# LM2576_BuckConverter.net
KiCad netlist of a schematic drawn in Altium Designer
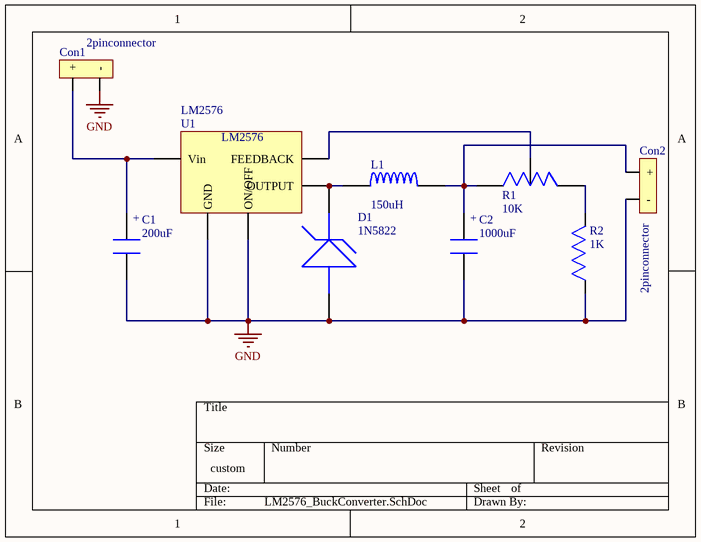
[diagram p0: LM2576_BuckConverter.SchDoc]

(export (version "E")
  (design (tool "Eeschema 10.0.6"))
  (components
    (comp (ref "C1")
      (value "200uF")
      (footprint "220uF Capacitor")
      (libsource (lib "LM2576_BuckConverter") (part "Electrolytic Cap 220uF"))
    )
    (comp (ref "C2")
      (value "1000uF")
      (footprint "1000Uf Cap")
      (libsource (lib "LM2576_BuckConverter") (part "Electrolytic Cap"))
    )
    (comp (ref "Con1")
      (value "2pinconnector")
      (footprint "2pin")
      (libsource (lib "LM2576_BuckConverter") (part "2pinconnector"))
    )
    (comp (ref "Con2")
      (value "2pinconnector")
      (footprint "2pin")
      (libsource (lib "") (part "2pinconnector_1"))
    )
    (comp (ref "D1")
      (value "1N5822")
      (footprint "1n5822")
      (libsource (lib "LM2576_BuckConverter") (part "1N5822"))
    )
    (comp (ref "L1")
      (value "150uH")
      (footprint "150uH Inductor")
      (libsource (lib "LM2576_BuckConverter") (part "150uH L"))
    )
    (comp (ref "R1")
      (value "10K")
      (footprint "10K Pot")
      (libsource (lib "LM2576_BuckConverter") (part "Variable Resistor"))
    )
    (comp (ref "R2")
      (value "1K")
      (footprint "1K 1206 Res")
      (libsource (lib "LM2576_BuckConverter") (part "Resistor"))
    )
    (comp (ref "U1")
      (value "LM2576")
      (footprint "LM2576-TO63-5")
      (libsource (lib "LM2576_BuckConverter") (part "LM2576"))
    )
  )
  (nets
    (net (code "1") (name "GND") (class "Default")
      (node (ref "C1") (pin "2") (pinfunction "2_2") (pintype "passive"))
      (node (ref "C2") (pin "2") (pinfunction "2_2") (pintype "passive"))
      (node (ref "Con1") (pin "2") (pinfunction "-_2") (pintype "passive"))
      (node (ref "Con2") (pin "2") (pinfunction "-_2") (pintype "passive"))
      (node (ref "D1") (pin "2") (pinfunction "2_2") (pintype "passive"))
      (node (ref "R2") (pin "1") (pinfunction "1_1") (pintype "passive"))
      (node (ref "U1") (pin "3") (pinfunction "GND_3") (pintype "passive"))
      (node (ref "U1") (pin "5") (pinfunction "ON/OFF_5") (pintype "passive"))
    )
    (net (code "2") (name "Net-(Con1-+)") (class "Default")
      (node (ref "C1") (pin "1") (pinfunction "1_1") (pintype "passive"))
      (node (ref "Con1") (pin "1") (pinfunction "+_1") (pintype "passive"))
      (node (ref "U1") (pin "1") (pinfunction "Vin_1") (pintype "passive"))
    )
    (net (code "3") (name "Net-(Con2-+)") (class "Default")
      (node (ref "C2") (pin "1") (pinfunction "1_1") (pintype "passive"))
      (node (ref "Con2") (pin "1") (pinfunction "+_1") (pintype "passive"))
      (node (ref "L1") (pin "2") (pinfunction "2_2") (pintype "passive"))
      (node (ref "R1") (pin "1") (pinfunction "1_1") (pintype "passive"))
    )
    (net (code "4") (name "Net-(R1-Pad3)") (class "Default")
      (node (ref "R1") (pin "3") (pinfunction "3_3") (pintype "passive"))
      (node (ref "R2") (pin "2") (pinfunction "2_2") (pintype "passive"))
    )
    (net (code "5") (name "Net-(U1-FEEDBACK)") (class "Default")
      (node (ref "R1") (pin "2") (pinfunction "2_2") (pintype "passive"))
      (node (ref "U1") (pin "4") (pinfunction "FEEDBACK_4") (pintype "passive"))
    )
    (net (code "6") (name "Net-(U1-OUTPUT)") (class "Default")
      (node (ref "D1") (pin "1") (pinfunction "1_1") (pintype "passive"))
      (node (ref "L1") (pin "1") (pinfunction "1_1") (pintype "passive"))
      (node (ref "U1") (pin "2") (pinfunction "OUTPUT_2") (pintype "passive"))
    )
  )
)
